# dpad.net
KiCad netlist of a schematic drawn in EAGLE
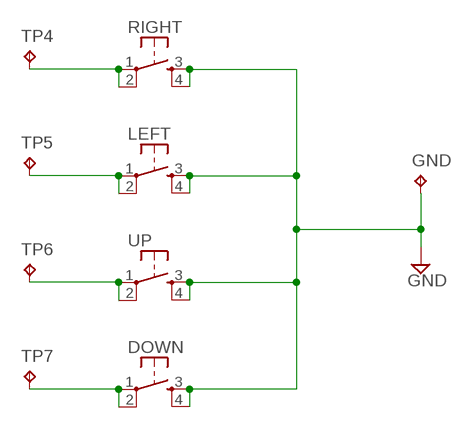
[diagram p0: schematic, sheet 1]

(export (version "E")
  (design (tool "Eeschema 10.0.6"))
  (components
    (comp (ref "DOWN")
      (value "BUTTON")
      (footprint "eagle-import:SMD_BUTTON")
      (fields (field (name "MPN") "B3F-1000"))
      (libsource (lib "eagle-import") (part "BUTTON"))
    )
    (comp (ref "GND")
      (value "TPPAD1-13")
      (footprint "eagle-import:P1-13")
      (libsource (lib "eagle-import") (part "TPPAD1-13"))
    )
    (comp (ref "LEFT")
      (value "BUTTON")
      (footprint "eagle-import:SMD_BUTTON")
      (fields (field (name "MPN") "B3F-1000"))
      (libsource (lib "eagle-import") (part "BUTTON"))
    )
    (comp (ref "RIGHT")
      (value "BUTTON")
      (footprint "eagle-import:SMD_BUTTON")
      (fields (field (name "MPN") "B3F-1000"))
      (libsource (lib "eagle-import") (part "BUTTON"))
    )
    (comp (ref "TP4")
      (value "TESTPAD")
      (footprint "eagle-import:TESTPAD")
      (libsource (lib "eagle-import") (part "TESTPAD"))
    )
    (comp (ref "TP5")
      (value "TESTPAD")
      (footprint "eagle-import:TESTPAD")
      (libsource (lib "eagle-import") (part "TESTPAD"))
    )
    (comp (ref "TP6")
      (value "TESTPAD")
      (footprint "eagle-import:TESTPAD")
      (libsource (lib "eagle-import") (part "TESTPAD"))
    )
    (comp (ref "TP7")
      (value "TESTPAD")
      (footprint "eagle-import:TESTPAD")
      (libsource (lib "eagle-import") (part "TESTPAD"))
    )
    (comp (ref "UP")
      (value "BUTTON")
      (footprint "eagle-import:SMD_BUTTON")
      (fields (field (name "MPN") "B3F-1000"))
      (libsource (lib "eagle-import") (part "BUTTON"))
    )
  )
  (nets
    (net (code "1") (name "GND") (class "Default")
      (node (ref "DOWN") (pin "3") (pinfunction "S_3") (pintype "passive"))
      (node (ref "DOWN") (pin "4") (pinfunction "S1_4") (pintype "passive"))
      (node (ref "GND") (pin "TP") (pinfunction "TP_TP") (pintype "input"))
      (node (ref "LEFT") (pin "3") (pinfunction "S_3") (pintype "passive"))
      (node (ref "LEFT") (pin "4") (pinfunction "S1_4") (pintype "passive"))
      (node (ref "RIGHT") (pin "3") (pinfunction "S_3") (pintype "passive"))
      (node (ref "RIGHT") (pin "4") (pinfunction "S1_4") (pintype "passive"))
      (node (ref "UP") (pin "3") (pinfunction "S_3") (pintype "passive"))
      (node (ref "UP") (pin "4") (pinfunction "S1_4") (pintype "passive"))
    )
    (net (code "2") (name "Net-(DOWN-P)") (class "Default")
      (node (ref "DOWN") (pin "1") (pinfunction "P_1") (pintype "passive"))
      (node (ref "DOWN") (pin "2") (pinfunction "P1_2") (pintype "passive"))
      (node (ref "TP7") (pin "P$1") (pinfunction "TP_P$1") (pintype "input"))
    )
    (net (code "3") (name "Net-(LEFT-P)") (class "Default")
      (node (ref "LEFT") (pin "1") (pinfunction "P_1") (pintype "passive"))
      (node (ref "LEFT") (pin "2") (pinfunction "P1_2") (pintype "passive"))
      (node (ref "TP5") (pin "P$1") (pinfunction "TP_P$1") (pintype "input"))
    )
    (net (code "4") (name "Net-(RIGHT-P)") (class "Default")
      (node (ref "RIGHT") (pin "1") (pinfunction "P_1") (pintype "passive"))
      (node (ref "RIGHT") (pin "2") (pinfunction "P1_2") (pintype "passive"))
      (node (ref "TP4") (pin "P$1") (pinfunction "TP_P$1") (pintype "input"))
    )
    (net (code "5") (name "Net-(TP6-TP)") (class "Default")
      (node (ref "TP6") (pin "P$1") (pinfunction "TP_P$1") (pintype "input"))
      (node (ref "UP") (pin "1") (pinfunction "P_1") (pintype "passive"))
      (node (ref "UP") (pin "2") (pinfunction "P1_2") (pintype "passive"))
    )
  )
)
